# CH3-Isolation.net
KiCad netlist of a schematic drawn in Altium Designer
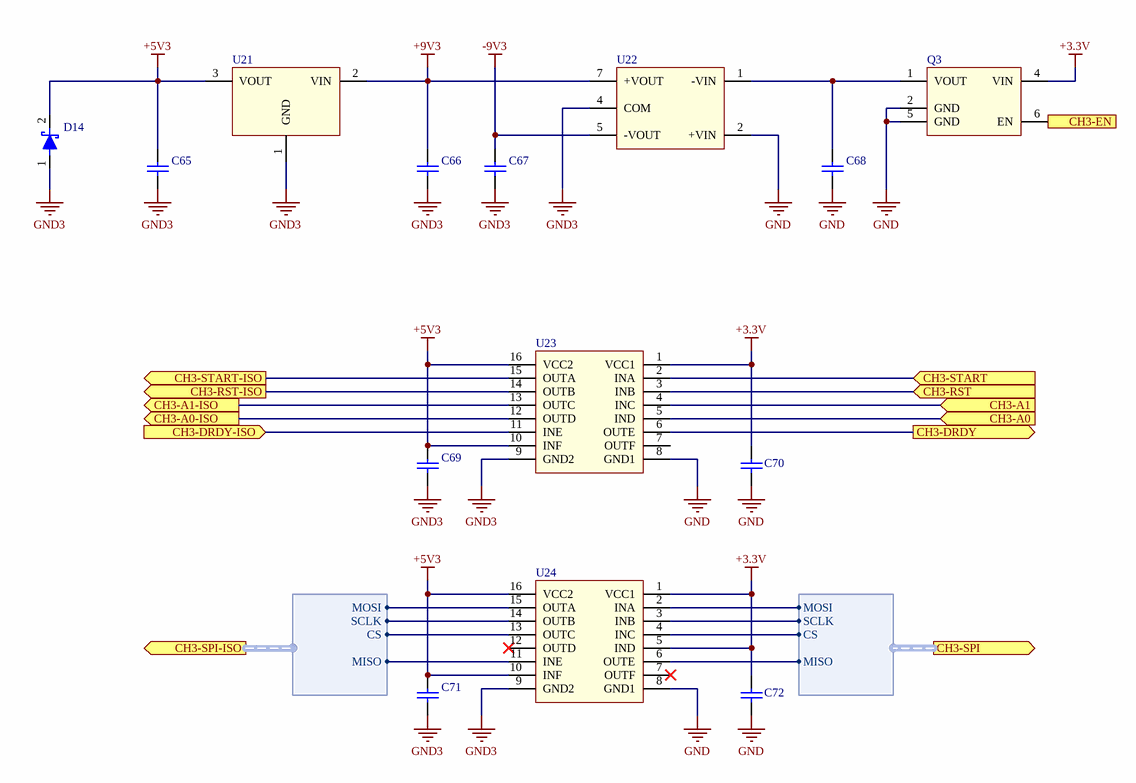
[diagram p0: CH3-Isolation.SchDoc]

(export (version "E")
  (design (tool "Eeschema 10.0.6"))
  (components
    (comp (ref "C65")
      (value "C0603C105M3RAC7867")
      (footprint "CAP-0603")
      (description "CAP CER 1uF 25V X7R 0603")
      (fields (field (name "MANUFACTURER") "Kemet") (field (name "TOLERANCE") "20%"))
      (libsource (lib "Kemet") (part "C0603C105M3RAC7867"))
    )
    (comp (ref "C66")
      (value "C0603C105M3RAC7867")
      (footprint "CAP-0603")
      (description "CAP CER 1uF 25V X7R 0603")
      (fields (field (name "MANUFACTURER") "Kemet") (field (name "TOLERANCE") "20%"))
      (libsource (lib "Kemet") (part "C0603C105M3RAC7867"))
    )
    (comp (ref "C67")
      (value "C0603C105M3RAC7867")
      (footprint "CAP-0603")
      (description "CAP CER 1uF 25V X7R 0603")
      (fields (field (name "MANUFACTURER") "Kemet") (field (name "TOLERANCE") "20%"))
      (libsource (lib "Kemet") (part "C0603C105M3RAC7867"))
    )
    (comp (ref "C68")
      (value "C0603C105M3RAC7867")
      (footprint "CAP-0603")
      (description "CAP CER 1uF 25V X7R 0603")
      (fields (field (name "MANUFACTURER") "Kemet") (field (name "TOLERANCE") "20%"))
      (libsource (lib "Kemet") (part "C0603C105M3RAC7867"))
    )
    (comp (ref "C69")
      (value "C0603C105M3RAC7867")
      (footprint "CAP-0603")
      (description "CAP CER 1uF 25V X7R 0603")
      (fields (field (name "MANUFACTURER") "Kemet") (field (name "TOLERANCE") "20%"))
      (libsource (lib "Kemet") (part "C0603C105M3RAC7867"))
    )
    (comp (ref "C70")
      (value "C0603C105M3RAC7867")
      (footprint "CAP-0603")
      (description "CAP CER 1uF 25V X7R 0603")
      (fields (field (name "MANUFACTURER") "Kemet") (field (name "TOLERANCE") "20%"))
      (libsource (lib "Kemet") (part "C0603C105M3RAC7867"))
    )
    (comp (ref "C71")
      (value "C0603C105M3RAC7867")
      (footprint "CAP-0603")
      (description "CAP CER 1uF 25V X7R 0603")
      (fields (field (name "MANUFACTURER") "Kemet") (field (name "TOLERANCE") "20%"))
      (libsource (lib "Kemet") (part "C0603C105M3RAC7867"))
    )
    (comp (ref "C72")
      (value "C0603C105M3RAC7867")
      (footprint "CAP-0603")
      (description "CAP CER 1uF 25V X7R 0603")
      (fields (field (name "MANUFACTURER") "Kemet") (field (name "TOLERANCE") "20%"))
      (libsource (lib "Kemet") (part "C0603C105M3RAC7867"))
    )
    (comp (ref "D14")
      (value "~")
      (footprint "SOD323 - DIODE UNIDIR")
      (description "Schottky Diode 30V 200mA SOT323")
      (fields (field (name "MANUFACTURER") "OnSemiconductor"))
      (libsource (lib "OnSemiconductors") (part "MM3Z5V6T1G"))
    )
    (comp (ref "Q3")
      (value "~")
      (footprint "TSSOP6")
      (fields (field (name "MANUFACTURER") "Microchip"))
      (libsource (lib "Microchip") (part "MIC94092YC6-TR"))
    )
    (comp (ref "U21")
      (value "~")
      (footprint "SOT23-5")
      (description "IC REG LDO 0.5V 0.15A TSOT23-5")
      (fields (field (name "MANUFACTURER") "ON Semiconductor"))
      (libsource (lib "OnSemiconductors") (part "NCP716BCSN500T1G"))
    )
    (comp (ref "U22")
      (value "R1D-3.309/P")
      (footprint "RECOM-R1D")
      (description "DC DC CONVERTER +/-9V 1W")
      (fields (field (name "MANUFACTURER") "Recom"))
      (libsource (lib "Recom") (part "R1D-3.309/P"))
    )
    (comp (ref "U23")
      (value "~")
      (footprint "SSOP16")
      (description "Digital Isolator, six-channel, 4/2, 16-SSOP")
      (fields (field (name "MANUFACTURER") "Texas Instruments"))
      (libsource (lib "TexasInstruments") (part "ISO7762FDBQ"))
    )
    (comp (ref "U24")
      (value "~")
      (footprint "SSOP16")
      (description "Digital Isolator, six-channel, 4/2, 16-SSOP")
      (fields (field (name "MANUFACTURER") "Texas Instruments"))
      (libsource (lib "TexasInstruments") (part "ISO7762FDBQ"))
    )
  )
  (nets
    (net (code "3") (name "+3.3V") (class "Default")
      (node (ref "C70") (pin "2") (pinfunction "2_2") (pintype "passive"))
      (node (ref "C72") (pin "2") (pinfunction "2_2") (pintype "passive"))
      (node (ref "Q3") (pin "4") (pinfunction "VIN_4") (pintype "passive"))
      (node (ref "U23") (pin "1") (pinfunction "VCC1_1") (pintype "passive"))
      (node (ref "U24") (pin "1") (pinfunction "VCC1_1") (pintype "passive"))
      (node (ref "U24") (pin "5") (pinfunction "IND_5") (pintype "passive"))
    )
    (net (code "4") (name "+5V3") (class "Default")
      (node (ref "C65") (pin "2") (pinfunction "2_2") (pintype "passive"))
      (node (ref "C69") (pin "2") (pinfunction "2_2") (pintype "passive"))
      (node (ref "C71") (pin "2") (pinfunction "2_2") (pintype "passive"))
      (node (ref "D14") (pin "2") (pinfunction "K_2") (pintype "passive"))
      (node (ref "U21") (pin "3") (pinfunction "VOUT_3") (pintype "passive"))
      (node (ref "U23") (pin "10") (pinfunction "INF_10") (pintype "passive"))
      (node (ref "U23") (pin "16") (pinfunction "VCC2_16") (pintype "passive"))
      (node (ref "U24") (pin "10") (pinfunction "INF_10") (pintype "passive"))
      (node (ref "U24") (pin "16") (pinfunction "VCC2_16") (pintype "passive"))
    )
    (net (code "5") (name "+9V3") (class "Default")
      (node (ref "C66") (pin "2") (pinfunction "2_2") (pintype "passive"))
      (node (ref "U21") (pin "2") (pinfunction "VIN_2") (pintype "passive"))
      (node (ref "U22") (pin "7") (pinfunction "+VOUT_7") (pintype "passive"))
    )
    (net (code "6") (name "-9V3") (class "Default")
      (node (ref "C67") (pin "2") (pinfunction "2_2") (pintype "passive"))
      (node (ref "U22") (pin "5") (pinfunction "-VOUT_5") (pintype "passive"))
    )
    (net (code "7") (name "/CH3-A0") (class "Default")
      (node (ref "U23") (pin "5") (pinfunction "IND_5") (pintype "passive"))
    )
    (net (code "8") (name "/CH3-A0-ISO") (class "Default")
      (node (ref "U23") (pin "12") (pinfunction "OUTD_12") (pintype "passive"))
    )
    (net (code "9") (name "/CH3-A1") (class "Default")
      (node (ref "U23") (pin "4") (pinfunction "INC_4") (pintype "passive"))
    )
    (net (code "10") (name "/CH3-A1-ISO") (class "Default")
      (node (ref "U23") (pin "13") (pinfunction "OUTC_13") (pintype "passive"))
    )
    (net (code "11") (name "/CH3-DRDY") (class "Default")
      (node (ref "U23") (pin "6") (pinfunction "OUTE_6") (pintype "passive"))
    )
    (net (code "12") (name "/CH3-DRDY-ISO") (class "Default")
      (node (ref "U23") (pin "11") (pinfunction "INE_11") (pintype "passive"))
    )
    (net (code "13") (name "/CH3-EN") (class "Default")
      (node (ref "Q3") (pin "6") (pinfunction "EN_6") (pintype "passive"))
    )
    (net (code "14") (name "/CH3-RST") (class "Default")
      (node (ref "U23") (pin "3") (pinfunction "INB_3") (pintype "passive"))
    )
    (net (code "15") (name "/CH3-RST-ISO") (class "Default")
      (node (ref "U23") (pin "14") (pinfunction "OUTB_14") (pintype "passive"))
    )
    (net (code "16") (name "/CH3-START") (class "Default")
      (node (ref "U23") (pin "2") (pinfunction "INA_2") (pintype "passive"))
    )
    (net (code "17") (name "/CH3-START-ISO") (class "Default")
      (node (ref "U23") (pin "15") (pinfunction "OUTA_15") (pintype "passive"))
    )
    (net (code "20") (name "GND") (class "Default")
      (node (ref "C68") (pin "1") (pinfunction "1_1") (pintype "passive"))
      (node (ref "C70") (pin "1") (pinfunction "1_1") (pintype "passive"))
      (node (ref "C72") (pin "1") (pinfunction "1_1") (pintype "passive"))
      (node (ref "Q3") (pin "2") (pinfunction "GND_2") (pintype "passive"))
      (node (ref "Q3") (pin "5") (pinfunction "GND_5") (pintype "passive"))
      (node (ref "U22") (pin "2") (pinfunction "+VIN_2") (pintype "passive"))
      (node (ref "U23") (pin "8") (pinfunction "GND1_8") (pintype "passive"))
      (node (ref "U24") (pin "8") (pinfunction "GND1_8") (pintype "passive"))
    )
    (net (code "21") (name "GND3") (class "Default")
      (node (ref "C65") (pin "1") (pinfunction "1_1") (pintype "passive"))
      (node (ref "C66") (pin "1") (pinfunction "1_1") (pintype "passive"))
      (node (ref "C67") (pin "1") (pinfunction "1_1") (pintype "passive"))
      (node (ref "C69") (pin "1") (pinfunction "1_1") (pintype "passive"))
      (node (ref "C71") (pin "1") (pinfunction "1_1") (pintype "passive"))
      (node (ref "D14") (pin "1") (pinfunction "A_1") (pintype "passive"))
      (node (ref "U21") (pin "1") (pinfunction "GND_1") (pintype "passive"))
      (node (ref "U22") (pin "4") (pinfunction "COM_4") (pintype "passive"))
      (node (ref "U23") (pin "9") (pinfunction "GND2_9") (pintype "passive"))
      (node (ref "U24") (pin "9") (pinfunction "GND2_9") (pintype "passive"))
    )
    (net (code "22") (name "Net-(Q3-VOUT)") (class "Default")
      (node (ref "C68") (pin "2") (pinfunction "2_2") (pintype "passive"))
      (node (ref "Q3") (pin "1") (pinfunction "VOUT_1") (pintype "passive"))
      (node (ref "U22") (pin "1") (pinfunction "-VIN_1") (pintype "passive"))
    )
    (net (code "23") (name "unconnected-(U23-OUTF-Pad7)") (class "Default")
      (node (ref "U23") (pin "7") (pinfunction "OUTF_7") (pintype "passive"))
    )
    (net (code "24") (name "unconnected-(U24-INA-Pad2)") (class "Default")
      (node (ref "U24") (pin "2") (pinfunction "INA_2") (pintype "passive"))
    )
    (net (code "25") (name "unconnected-(U24-INB-Pad3)") (class "Default")
      (node (ref "U24") (pin "3") (pinfunction "INB_3") (pintype "passive"))
    )
    (net (code "26") (name "unconnected-(U24-INC-Pad4)") (class "Default")
      (node (ref "U24") (pin "4") (pinfunction "INC_4") (pintype "passive"))
    )
    (net (code "27") (name "unconnected-(U24-INE-Pad11)") (class "Default")
      (node (ref "U24") (pin "11") (pinfunction "INE_11") (pintype "passive"))
    )
    (net (code "28") (name "unconnected-(U24-OUTA-Pad15)") (class "Default")
      (node (ref "U24") (pin "15") (pinfunction "OUTA_15") (pintype "passive"))
    )
    (net (code "29") (name "unconnected-(U24-OUTB-Pad14)") (class "Default")
      (node (ref "U24") (pin "14") (pinfunction "OUTB_14") (pintype "passive"))
    )
    (net (code "30") (name "unconnected-(U24-OUTC-Pad13)") (class "Default")
      (node (ref "U24") (pin "13") (pinfunction "OUTC_13") (pintype "passive"))
    )
    (net (code "31") (name "unconnected-(U24-OUTD-Pad12)") (class "Default")
      (node (ref "U24") (pin "12") (pinfunction "OUTD_12") (pintype "passive+no_connect"))
    )
    (net (code "32") (name "unconnected-(U24-OUTE-Pad6)") (class "Default")
      (node (ref "U24") (pin "6") (pinfunction "OUTE_6") (pintype "passive"))
    )
    (net (code "33") (name "unconnected-(U24-OUTF-Pad7)") (class "Default")
      (node (ref "U24") (pin "7") (pinfunction "OUTF_7") (pintype "passive+no_connect"))
    )
  )
)
